# Codeshelf-0012_v01.net
KiCad netlist of a schematic drawn in EAGLE
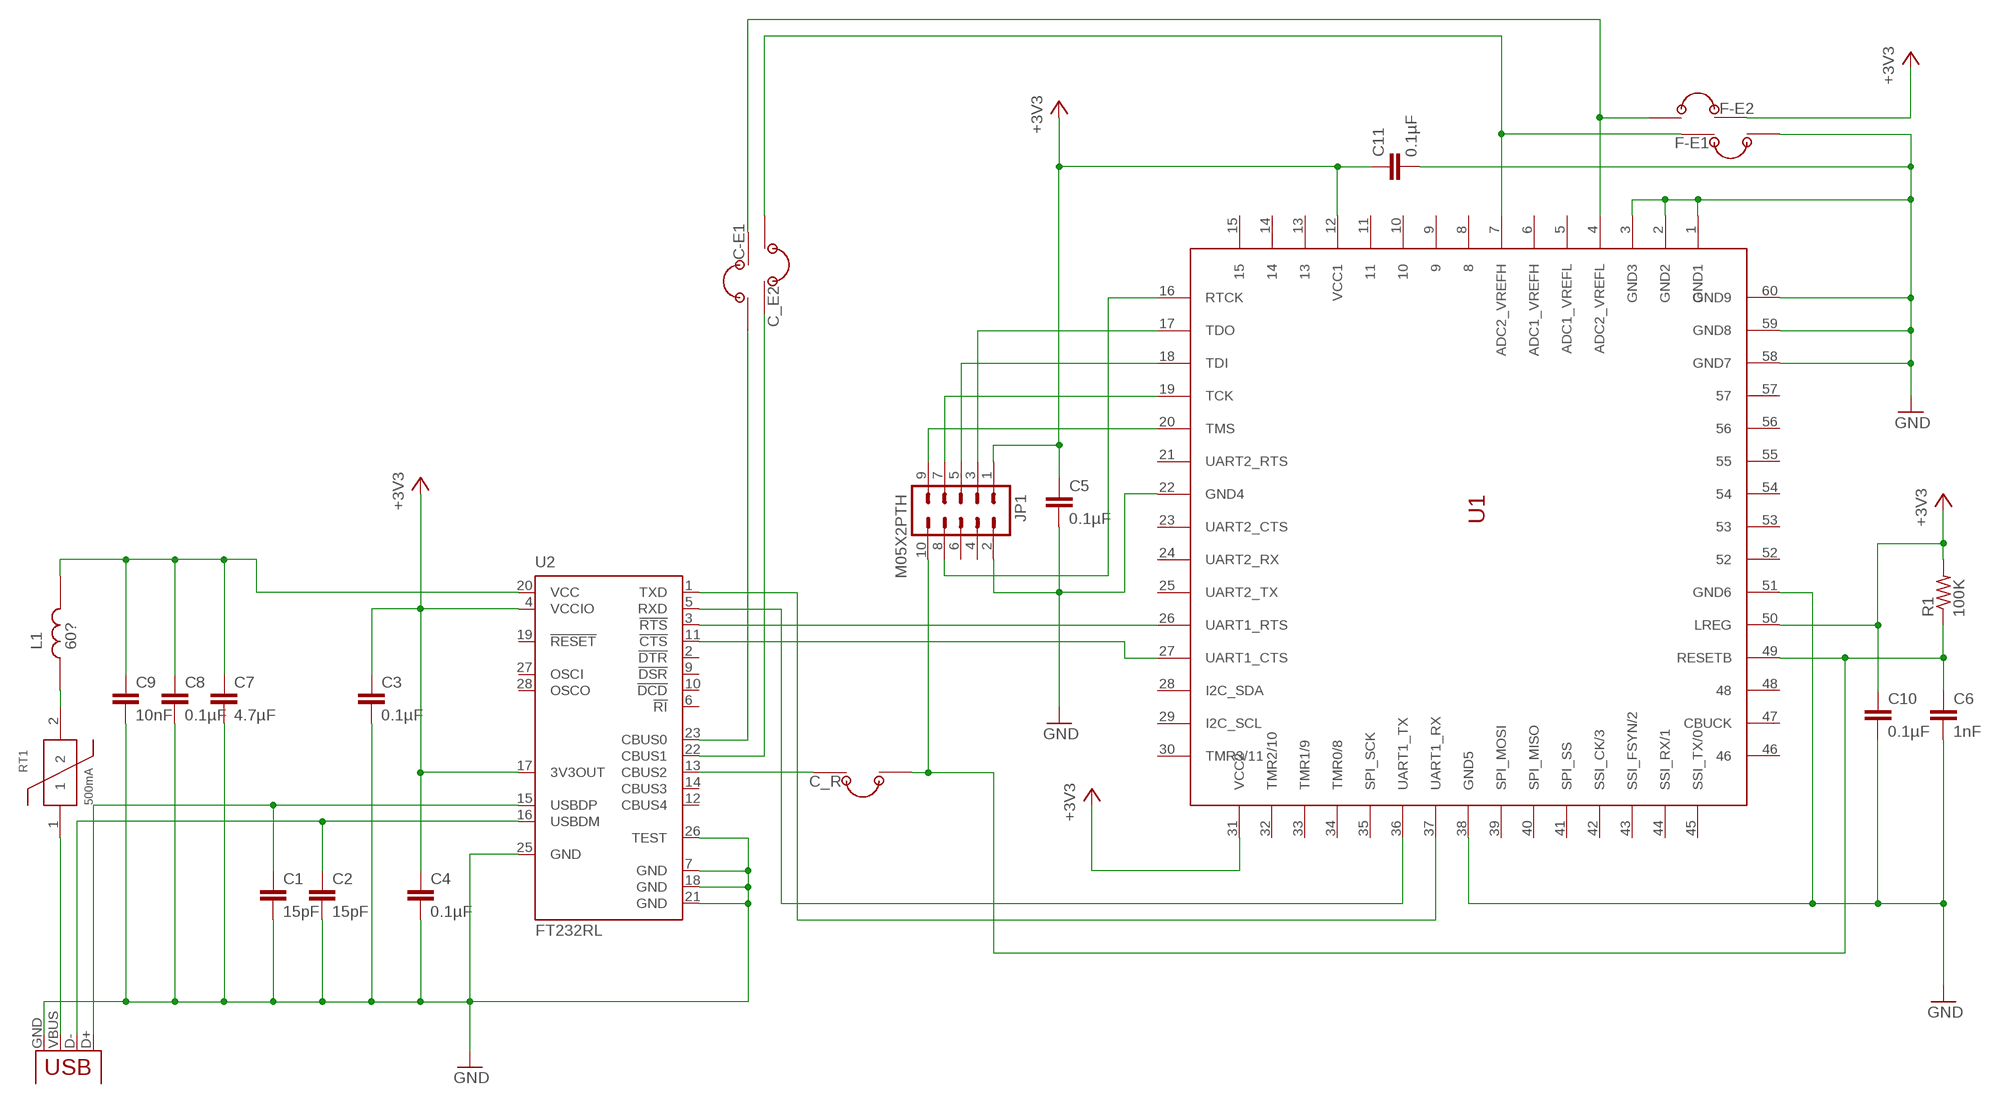
[diagram p0: schematic, sheet 1]

(export (version "E")
  (design (tool "Eeschema 10.0.6"))
  (components
    (comp (ref "C-E1")
      (value "JUMPER-2X-SMT-VIA")
      (footprint "eagle-import:JUMPER-VIA-2X")
      (libsource (lib "eagle-import") (part "JUMPER-2X-SMT-VIA"))
    )
    (comp (ref "C1")
      (value "15pF")
      (footprint "eagle-import:C0402")
      (libsource (lib "eagle-import") (part "RF-C0402"))
    )
    (comp (ref "C2")
      (value "15pF")
      (footprint "eagle-import:C0402")
      (libsource (lib "eagle-import") (part "RF-C0402"))
    )
    (comp (ref "C3")
      (value "0.1µF")
      (footprint "eagle-import:C0402")
      (libsource (lib "eagle-import") (part "RF-C0402"))
    )
    (comp (ref "C4")
      (value "0.1µF")
      (footprint "eagle-import:C0402")
      (libsource (lib "eagle-import") (part "RF-C0402"))
    )
    (comp (ref "C5")
      (value "0.1µF")
      (footprint "eagle-import:C0402")
      (libsource (lib "eagle-import") (part "RF-C0402"))
    )
    (comp (ref "C6")
      (value "1nF")
      (footprint "eagle-import:C0402")
      (libsource (lib "eagle-import") (part "RF-C0402"))
    )
    (comp (ref "C7")
      (value "4.7µF")
      (footprint "eagle-import:C0805")
      (libsource (lib "eagle-import") (part "RF-C0805"))
    )
    (comp (ref "C8")
      (value "0.1µF")
      (footprint "eagle-import:C0402")
      (libsource (lib "eagle-import") (part "RF-C0402"))
    )
    (comp (ref "C9")
      (value "10nF")
      (footprint "eagle-import:C0402")
      (libsource (lib "eagle-import") (part "RF-C0402"))
    )
    (comp (ref "C10")
      (value "0.1µF")
      (footprint "eagle-import:C0402")
      (libsource (lib "eagle-import") (part "RF-C0402"))
    )
    (comp (ref "C11")
      (value "0.1µF")
      (footprint "eagle-import:C0402")
      (libsource (lib "eagle-import") (part "RF-C0402"))
    )
    (comp (ref "C_E2")
      (value "JUMPER-2X-SMT-VIA")
      (footprint "eagle-import:JUMPER-VIA-2X")
      (libsource (lib "eagle-import") (part "JUMPER-2X-SMT-VIA"))
    )
    (comp (ref "C_R")
      (value "JUMPER-2X-SMT-VIA")
      (footprint "eagle-import:JUMPER-VIA-2X")
      (libsource (lib "eagle-import") (part "JUMPER-2X-SMT-VIA"))
    )
    (comp (ref "F-E1")
      (value "JUMPER-2X-SMT-VIA")
      (footprint "eagle-import:JUMPER-VIA-2X")
      (libsource (lib "eagle-import") (part "JUMPER-2X-SMT-VIA"))
    )
    (comp (ref "F-E2")
      (value "JUMPER-2X-SMT-VIA")
      (footprint "eagle-import:JUMPER-VIA-2X")
      (libsource (lib "eagle-import") (part "JUMPER-2X-SMT-VIA"))
    )
    (comp (ref "JP1")
      (value "M05X2PTH")
      (footprint "eagle-import:AVR_ICSP")
      (libsource (lib "eagle-import") (part "M05X2PTH"))
    )
    (comp (ref "L1")
      (value "60?")
      (footprint "eagle-import:RF-L0603")
      (libsource (lib "eagle-import") (part "RF-L0603"))
    )
    (comp (ref "R1")
      (value "100K")
      (footprint "eagle-import:RF-R0402")
      (libsource (lib "eagle-import") (part "RF-R0402"))
    )
    (comp (ref "RT1")
      (value "500mA")
      (footprint "eagle-import:C1210")
      (libsource (lib "eagle-import") (part "SMD050F"))
    )
    (comp (ref "U1")
      (value "ZSFM201-1A")
      (footprint "eagle-import:ZSFM201-1")
      (libsource (lib "eagle-import") (part "ZSFM201-1A"))
    )
    (comp (ref "U2")
      (value "FT232RL")
      (footprint "eagle-import:SSOP28")
      (libsource (lib "eagle-import") (part "FT232RL"))
    )
    (comp (ref "X1")
      (value "USBPTH")
      (footprint "eagle-import:USB-B-PTH")
      (libsource (lib "eagle-import") (part "USBPTH"))
    )
  )
  (nets
    (net (code "1") (name "+3V3") (class "Default")
      (node (ref "C10") (pin "1") (pinfunction "1_1") (pintype "passive"))
      (node (ref "C11") (pin "1") (pinfunction "1_1") (pintype "passive"))
      (node (ref "C3") (pin "1") (pinfunction "1_1") (pintype "passive"))
      (node (ref "C4") (pin "1") (pinfunction "1_1") (pintype "passive"))
      (node (ref "C5") (pin "1") (pinfunction "1_1") (pintype "passive"))
      (node (ref "F-E2") (pin "2") (pinfunction "2_2") (pintype "bidirectional"))
      (node (ref "JP1") (pin "1") (pinfunction "1_1") (pintype "passive"))
      (node (ref "R1") (pin "2") (pinfunction "2_2") (pintype "passive"))
      (node (ref "U1") (pin "12") (pinfunction "VCC1_12") (pintype "power_in"))
      (node (ref "U1") (pin "31") (pinfunction "VCC2_31") (pintype "power_in"))
      (node (ref "U1") (pin "50") (pinfunction "LREG_50") (pintype "bidirectional"))
      (node (ref "U2") (pin "17") (pinfunction "3V3OUT_17") (pintype "output"))
      (node (ref "U2") (pin "4") (pinfunction "VCCIO_4") (pintype "power_in"))
    )
    (net (code "2") (name "GND") (class "Default")
      (node (ref "C1") (pin "2") (pinfunction "2_2") (pintype "passive"))
      (node (ref "C10") (pin "2") (pinfunction "2_2") (pintype "passive"))
      (node (ref "C11") (pin "2") (pinfunction "2_2") (pintype "passive"))
      (node (ref "C2") (pin "2") (pinfunction "2_2") (pintype "passive"))
      (node (ref "C3") (pin "2") (pinfunction "2_2") (pintype "passive"))
      (node (ref "C4") (pin "2") (pinfunction "2_2") (pintype "passive"))
      (node (ref "C5") (pin "2") (pinfunction "2_2") (pintype "passive"))
      (node (ref "C6") (pin "2") (pinfunction "2_2") (pintype "passive"))
      (node (ref "C7") (pin "2") (pinfunction "2_2") (pintype "passive"))
      (node (ref "C8") (pin "2") (pinfunction "2_2") (pintype "passive"))
      (node (ref "C9") (pin "2") (pinfunction "2_2") (pintype "passive"))
      (node (ref "F-E1") (pin "1") (pinfunction "1_1") (pintype "bidirectional"))
      (node (ref "JP1") (pin "2") (pinfunction "2_2") (pintype "passive"))
      (node (ref "U1") (pin "1") (pinfunction "GND1_1") (pintype "power_in"))
      (node (ref "U1") (pin "2") (pinfunction "GND2_2") (pintype "power_in"))
      (node (ref "U1") (pin "22") (pinfunction "GND4_22") (pintype "power_in"))
      (node (ref "U1") (pin "3") (pinfunction "GND3_3") (pintype "power_in"))
      (node (ref "U1") (pin "38") (pinfunction "GND5_38") (pintype "power_in"))
      (node (ref "U1") (pin "51") (pinfunction "GND6_51") (pintype "power_in"))
      (node (ref "U1") (pin "58") (pinfunction "GND7_58") (pintype "power_in"))
      (node (ref "U1") (pin "59") (pinfunction "GND8_59") (pintype "power_in"))
      (node (ref "U1") (pin "60") (pinfunction "GND9_60") (pintype "power_in"))
      (node (ref "U2") (pin "18") (pinfunction "GND_18") (pintype "power_in"))
      (node (ref "U2") (pin "21") (pinfunction "GND_21") (pintype "power_in"))
      (node (ref "U2") (pin "25") (pinfunction "GND_25") (pintype "power_in"))
      (node (ref "U2") (pin "26") (pinfunction "TEST_26") (pintype "input"))
      (node (ref "U2") (pin "7") (pinfunction "GND_7") (pintype "power_in"))
      (node (ref "X1") (pin "GND") (pinfunction "GND_GND") (pintype "bidirectional"))
    )
    (net (code "3") (name "Net-(L1-Pad2)") (class "Default")
      (node (ref "L1") (pin "2") (pinfunction "2_2") (pintype "bidirectional"))
      (node (ref "RT1") (pin "2") (pinfunction "2_2") (pintype "bidirectional"))
    )
    (net (code "4") (name "Net-(RT1-Pad1)") (class "Default")
      (node (ref "RT1") (pin "1") (pinfunction "1_1") (pintype "bidirectional"))
      (node (ref "X1") (pin "VBUS") (pinfunction "VBUS_VBUS") (pintype "bidirectional"))
    )
    (net (code "5") (name "Net-(U1-ADC2_VREFH)") (class "Default")
      (node (ref "C_E2") (pin "1") (pinfunction "1_1") (pintype "bidirectional"))
      (node (ref "F-E1") (pin "2") (pinfunction "2_2") (pintype "bidirectional"))
      (node (ref "U1") (pin "7") (pinfunction "ADC2_VREFH_7") (pintype "bidirectional"))
    )
    (net (code "6") (name "Net-(U1-ADC2_VREFL)") (class "Default")
      (node (ref "C-E1") (pin "2") (pinfunction "2_2") (pintype "bidirectional"))
      (node (ref "F-E2") (pin "1") (pinfunction "1_1") (pintype "bidirectional"))
      (node (ref "U1") (pin "4") (pinfunction "ADC2_VREFL_4") (pintype "bidirectional"))
    )
    (net (code "7") (name "Net-(U1-RESETB)") (class "Default")
      (node (ref "C6") (pin "1") (pinfunction "1_1") (pintype "passive"))
      (node (ref "C_R") (pin "1") (pinfunction "1_1") (pintype "bidirectional"))
      (node (ref "JP1") (pin "10") (pinfunction "10_10") (pintype "passive"))
      (node (ref "R1") (pin "1") (pinfunction "1_1") (pintype "passive"))
      (node (ref "U1") (pin "49") (pinfunction "RESETB_49") (pintype "bidirectional"))
    )
    (net (code "8") (name "Net-(U1-RTCK)") (class "Default")
      (node (ref "JP1") (pin "8") (pinfunction "8_8") (pintype "passive"))
      (node (ref "U1") (pin "16") (pinfunction "RTCK_16") (pintype "bidirectional"))
    )
    (net (code "9") (name "Net-(U1-TCK)") (class "Default")
      (node (ref "JP1") (pin "7") (pinfunction "7_7") (pintype "passive"))
      (node (ref "U1") (pin "19") (pinfunction "TCK_19") (pintype "bidirectional"))
    )
    (net (code "10") (name "Net-(U1-TDI)") (class "Default")
      (node (ref "JP1") (pin "5") (pinfunction "5_5") (pintype "passive"))
      (node (ref "U1") (pin "18") (pinfunction "TDI_18") (pintype "bidirectional"))
    )
    (net (code "11") (name "Net-(U1-TDO)") (class "Default")
      (node (ref "JP1") (pin "3") (pinfunction "3_3") (pintype "passive"))
      (node (ref "U1") (pin "17") (pinfunction "TDO_17") (pintype "bidirectional"))
    )
    (net (code "12") (name "Net-(U1-TMS)") (class "Default")
      (node (ref "JP1") (pin "9") (pinfunction "9_9") (pintype "passive"))
      (node (ref "U1") (pin "20") (pinfunction "TMS_20") (pintype "bidirectional"))
    )
    (net (code "13") (name "Net-(U1-UART1_CTS)") (class "Default")
      (node (ref "U1") (pin "27") (pinfunction "UART1_CTS_27") (pintype "bidirectional"))
      (node (ref "U2") (pin "11") (pinfunction "~{CTS}_11") (pintype "input"))
    )
    (net (code "14") (name "Net-(U1-UART1_RTS)") (class "Default")
      (node (ref "U1") (pin "26") (pinfunction "UART1_RTS_26") (pintype "bidirectional"))
      (node (ref "U2") (pin "3") (pinfunction "~{RTS}_3") (pintype "output"))
    )
    (net (code "15") (name "Net-(U1-UART1_RX)") (class "Default")
      (node (ref "U1") (pin "37") (pinfunction "UART1_RX_37") (pintype "bidirectional"))
      (node (ref "U2") (pin "1") (pinfunction "TXD_1") (pintype "output"))
    )
    (net (code "16") (name "Net-(U1-UART1_TX)") (class "Default")
      (node (ref "U1") (pin "36") (pinfunction "UART1_TX_36") (pintype "bidirectional"))
      (node (ref "U2") (pin "5") (pinfunction "RXD_5") (pintype "input"))
    )
    (net (code "17") (name "Net-(U2-CBUS0)") (class "Default")
      (node (ref "C-E1") (pin "1") (pinfunction "1_1") (pintype "bidirectional"))
      (node (ref "U2") (pin "23") (pinfunction "CBUS0_23") (pintype "bidirectional"))
    )
    (net (code "18") (name "Net-(U2-CBUS1)") (class "Default")
      (node (ref "C_E2") (pin "2") (pinfunction "2_2") (pintype "bidirectional"))
      (node (ref "U2") (pin "22") (pinfunction "CBUS1_22") (pintype "bidirectional"))
    )
    (net (code "19") (name "Net-(U2-CBUS2)") (class "Default")
      (node (ref "C_R") (pin "2") (pinfunction "2_2") (pintype "bidirectional"))
      (node (ref "U2") (pin "13") (pinfunction "CBUS2_13") (pintype "bidirectional"))
    )
    (net (code "20") (name "Net-(U2-USBDM)") (class "Default")
      (node (ref "C2") (pin "1") (pinfunction "1_1") (pintype "passive"))
      (node (ref "U2") (pin "16") (pinfunction "USBDM_16") (pintype "bidirectional"))
      (node (ref "X1") (pin "D-") (pinfunction "D-_D-") (pintype "bidirectional"))
    )
    (net (code "21") (name "Net-(U2-USBDP)") (class "Default")
      (node (ref "C1") (pin "1") (pinfunction "1_1") (pintype "passive"))
      (node (ref "U2") (pin "15") (pinfunction "USBDP_15") (pintype "bidirectional"))
      (node (ref "X1") (pin "D+") (pinfunction "D+_D+") (pintype "bidirectional"))
    )
    (net (code "22") (name "Net-(U2-VCC)") (class "Default")
      (node (ref "C7") (pin "1") (pinfunction "1_1") (pintype "passive"))
      (node (ref "C8") (pin "1") (pinfunction "1_1") (pintype "passive"))
      (node (ref "C9") (pin "1") (pinfunction "1_1") (pintype "passive"))
      (node (ref "L1") (pin "1") (pinfunction "1_1") (pintype "bidirectional"))
      (node (ref "U2") (pin "20") (pinfunction "VCC_20") (pintype "power_in"))
    )
    (net (code "23") (name "unconnected-(JP1-Pad4)") (class "Default")
      (node (ref "JP1") (pin "4") (pinfunction "4_4") (pintype "passive"))
    )
    (net (code "24") (name "unconnected-(JP1-Pad6)") (class "Default")
      (node (ref "JP1") (pin "6") (pinfunction "6_6") (pintype "passive"))
    )
    (net (code "25") (name "unconnected-(U1-ADC1_VREFH-Pad6)") (class "Default")
      (node (ref "U1") (pin "6") (pinfunction "ADC1_VREFH_6") (pintype "bidirectional"))
    )
    (net (code "26") (name "unconnected-(U1-ADC1_VREFL-Pad5)") (class "Default")
      (node (ref "U1") (pin "5") (pinfunction "ADC1_VREFL_5") (pintype "bidirectional"))
    )
    (net (code "27") (name "unconnected-(U1-CBUCK-Pad47)") (class "Default")
      (node (ref "U1") (pin "47") (pinfunction "CBUCK_47") (pintype "bidirectional"))
    )
    (net (code "28") (name "unconnected-(U1-I2C_SCL-Pad29)") (class "Default")
      (node (ref "U1") (pin "29") (pinfunction "I2C_SCL_29") (pintype "bidirectional"))
    )
    (net (code "29") (name "unconnected-(U1-I2C_SDA-Pad28)") (class "Default")
      (node (ref "U1") (pin "28") (pinfunction "I2C_SDA_28") (pintype "bidirectional"))
    )
    (net (code "30") (name "unconnected-(U1-Pad8)") (class "Default")
      (node (ref "U1") (pin "8") (pinfunction "8_8") (pintype "bidirectional"))
    )
    (net (code "31") (name "unconnected-(U1-Pad9)") (class "Default")
      (node (ref "U1") (pin "9") (pinfunction "9_9") (pintype "bidirectional"))
    )
    (net (code "32") (name "unconnected-(U1-Pad10)") (class "Default")
      (node (ref "U1") (pin "10") (pinfunction "10_10") (pintype "bidirectional"))
    )
    (net (code "33") (name "unconnected-(U1-Pad11)") (class "Default")
      (node (ref "U1") (pin "11") (pinfunction "11_11") (pintype "bidirectional"))
    )
    (net (code "34") (name "unconnected-(U1-Pad13)") (class "Default")
      (node (ref "U1") (pin "13") (pinfunction "13_13") (pintype "bidirectional"))
    )
    (net (code "35") (name "unconnected-(U1-Pad14)") (class "Default")
      (node (ref "U1") (pin "14") (pinfunction "14_14") (pintype "bidirectional"))
    )
    (net (code "36") (name "unconnected-(U1-Pad15)") (class "Default")
      (node (ref "U1") (pin "15") (pinfunction "15_15") (pintype "bidirectional"))
    )
    (net (code "37") (name "unconnected-(U1-Pad46)") (class "Default")
      (node (ref "U1") (pin "46") (pinfunction "46_46") (pintype "bidirectional"))
    )
    (net (code "38") (name "unconnected-(U1-Pad48)") (class "Default")
      (node (ref "U1") (pin "48") (pinfunction "48_48") (pintype "bidirectional"))
    )
    (net (code "39") (name "unconnected-(U1-Pad52)") (class "Default")
      (node (ref "U1") (pin "52") (pinfunction "52_52") (pintype "bidirectional"))
    )
    (net (code "40") (name "unconnected-(U1-Pad53)") (class "Default")
      (node (ref "U1") (pin "53") (pinfunction "53_53") (pintype "bidirectional"))
    )
    (net (code "41") (name "unconnected-(U1-Pad54)") (class "Default")
      (node (ref "U1") (pin "54") (pinfunction "54_54") (pintype "bidirectional"))
    )
    (net (code "42") (name "unconnected-(U1-Pad55)") (class "Default")
      (node (ref "U1") (pin "55") (pinfunction "55_55") (pintype "bidirectional"))
    )
    (net (code "43") (name "unconnected-(U1-Pad56)") (class "Default")
      (node (ref "U1") (pin "56") (pinfunction "56_56") (pintype "bidirectional"))
    )
    (net (code "44") (name "unconnected-(U1-Pad57)") (class "Default")
      (node (ref "U1") (pin "57") (pinfunction "57_57") (pintype "bidirectional"))
    )
    (net (code "45") (name "unconnected-(U1-SPI_MISO-Pad40)") (class "Default")
      (node (ref "U1") (pin "40") (pinfunction "SPI_MISO_40") (pintype "bidirectional"))
    )
    (net (code "46") (name "unconnected-(U1-SPI_MOSI-Pad39)") (class "Default")
      (node (ref "U1") (pin "39") (pinfunction "SPI_MOSI_39") (pintype "bidirectional"))
    )
    (net (code "47") (name "unconnected-(U1-SPI_SCK-Pad35)") (class "Default")
      (node (ref "U1") (pin "35") (pinfunction "SPI_SCK_35") (pintype "bidirectional"))
    )
    (net (code "48") (name "unconnected-(U1-SPI_SS-Pad41)") (class "Default")
      (node (ref "U1") (pin "41") (pinfunction "SPI_SS_41") (pintype "bidirectional"))
    )
    (net (code "49") (name "unconnected-(U1-SSI_CK{slash}3-Pad42)") (class "Default")
      (node (ref "U1") (pin "42") (pinfunction "SSI_CK/3_42") (pintype "bidirectional"))
    )
    (net (code "50") (name "unconnected-(U1-SSI_FSYN{slash}2-Pad43)") (class "Default")
      (node (ref "U1") (pin "43") (pinfunction "SSI_FSYN/2_43") (pintype "bidirectional"))
    )
    (net (code "51") (name "unconnected-(U1-SSI_RX{slash}1-Pad44)") (class "Default")
      (node (ref "U1") (pin "44") (pinfunction "SSI_RX/1_44") (pintype "bidirectional"))
    )
    (net (code "52") (name "unconnected-(U1-SSI_TX{slash}0-Pad45)") (class "Default")
      (node (ref "U1") (pin "45") (pinfunction "SSI_TX/0_45") (pintype "bidirectional"))
    )
    (net (code "53") (name "unconnected-(U1-TMR0{slash}8-Pad34)") (class "Default")
      (node (ref "U1") (pin "34") (pinfunction "TMR0/8_34") (pintype "bidirectional"))
    )
    (net (code "54") (name "unconnected-(U1-TMR1{slash}9-Pad33)") (class "Default")
      (node (ref "U1") (pin "33") (pinfunction "TMR1/9_33") (pintype "bidirectional"))
    )
    (net (code "55") (name "unconnected-(U1-TMR2{slash}10-Pad32)") (class "Default")
      (node (ref "U1") (pin "32") (pinfunction "TMR2/10_32") (pintype "bidirectional"))
    )
    (net (code "56") (name "unconnected-(U1-TMR3{slash}11-Pad30)") (class "Default")
      (node (ref "U1") (pin "30") (pinfunction "TMR3/11_30") (pintype "bidirectional"))
    )
    (net (code "57") (name "unconnected-(U1-UART2_CTS-Pad23)") (class "Default")
      (node (ref "U1") (pin "23") (pinfunction "UART2_CTS_23") (pintype "bidirectional"))
    )
    (net (code "58") (name "unconnected-(U1-UART2_RTS-Pad21)") (class "Default")
      (node (ref "U1") (pin "21") (pinfunction "UART2_RTS_21") (pintype "bidirectional"))
    )
    (net (code "59") (name "unconnected-(U1-UART2_RX-Pad24)") (class "Default")
      (node (ref "U1") (pin "24") (pinfunction "UART2_RX_24") (pintype "bidirectional"))
    )
    (net (code "60") (name "unconnected-(U1-UART2_TX-Pad25)") (class "Default")
      (node (ref "U1") (pin "25") (pinfunction "UART2_TX_25") (pintype "bidirectional"))
    )
    (net (code "61") (name "unconnected-(U2-CBUS3-Pad14)") (class "Default")
      (node (ref "U2") (pin "14") (pinfunction "CBUS3_14") (pintype "bidirectional"))
    )
    (net (code "62") (name "unconnected-(U2-CBUS4-Pad12)") (class "Default")
      (node (ref "U2") (pin "12") (pinfunction "CBUS4_12") (pintype "bidirectional"))
    )
    (net (code "63") (name "unconnected-(U2-OSCI-Pad27)") (class "Default")
      (node (ref "U2") (pin "27") (pinfunction "OSCI_27") (pintype "input"))
    )
    (net (code "64") (name "unconnected-(U2-OSCO-Pad28)") (class "Default")
      (node (ref "U2") (pin "28") (pinfunction "OSCO_28") (pintype "output"))
    )
    (net (code "65") (name "unconnected-(U2-~{DCD}-Pad10)") (class "Default")
      (node (ref "U2") (pin "10") (pinfunction "~{DCD}_10") (pintype "input"))
    )
    (net (code "66") (name "unconnected-(U2-~{DSR}-Pad9)") (class "Default")
      (node (ref "U2") (pin "9") (pinfunction "~{DSR}_9") (pintype "input"))
    )
    (net (code "67") (name "unconnected-(U2-~{DTR}-Pad2)") (class "Default")
      (node (ref "U2") (pin "2") (pinfunction "~{DTR}_2") (pintype "output"))
    )
    (net (code "68") (name "unconnected-(U2-~{RESET}-Pad19)") (class "Default")
      (node (ref "U2") (pin "19") (pinfunction "~{RESET}_19") (pintype "input"))
    )
    (net (code "69") (name "unconnected-(U2-~{RI}-Pad6)") (class "Default")
      (node (ref "U2") (pin "6") (pinfunction "~{RI}_6") (pintype "input"))
    )
  )
)
